# sch_camera.net
KiCad netlist of a schematic drawn in Altium Designer
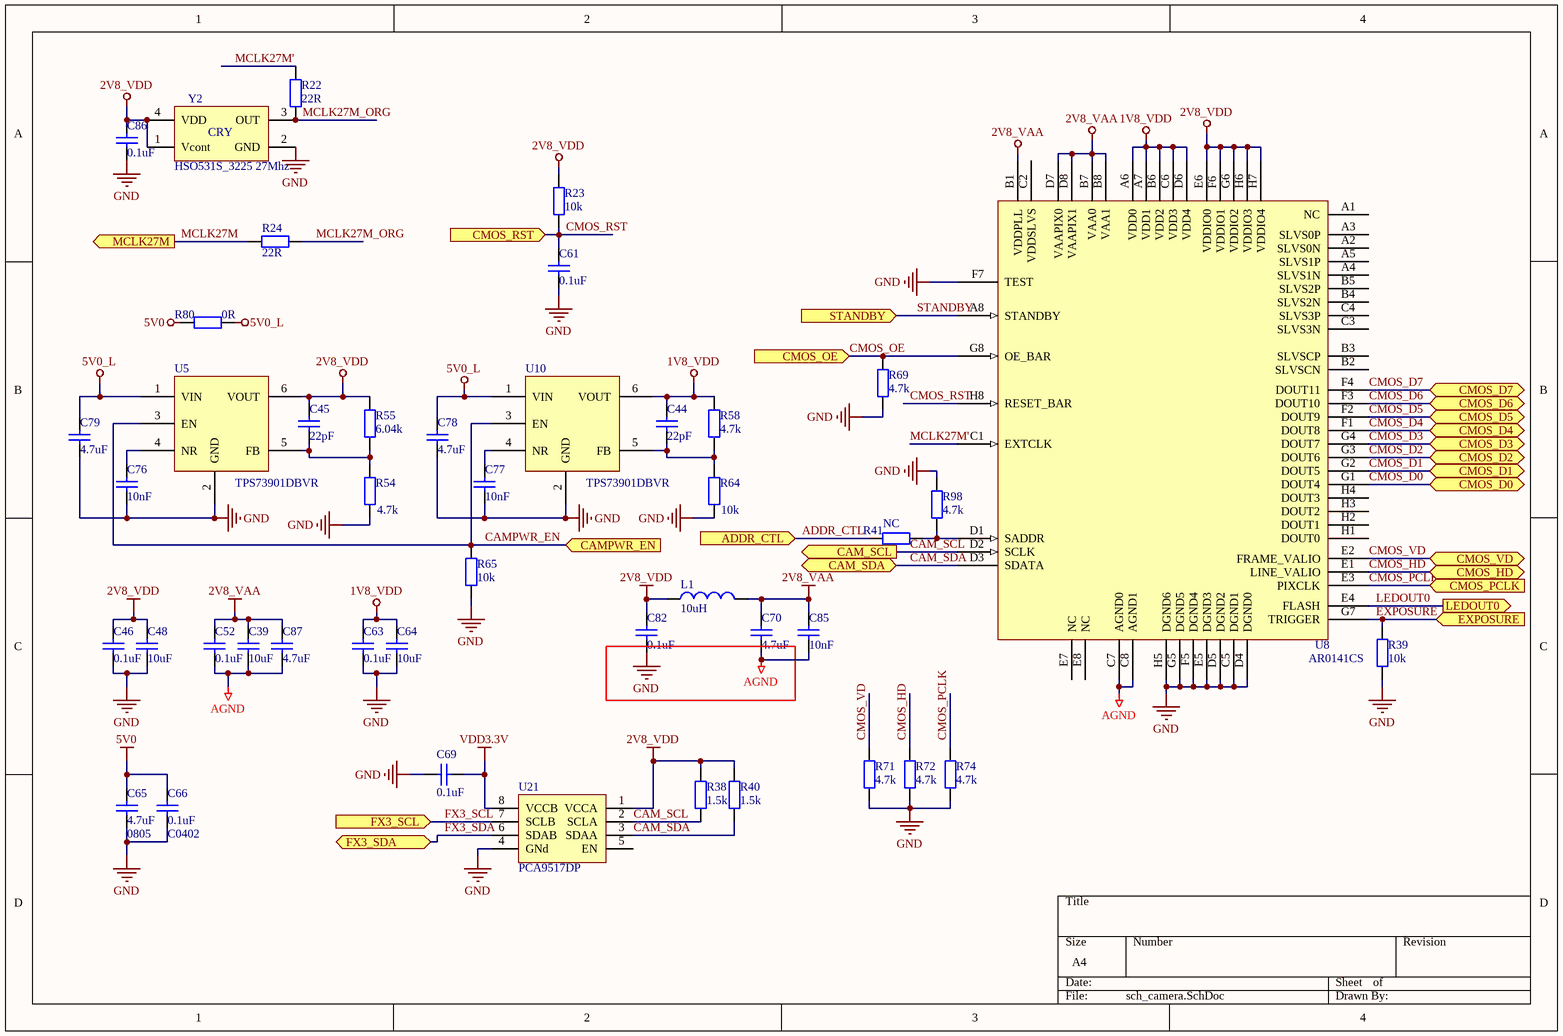
[diagram p0: sch_camera.SchDoc]

(export (version "E")
  (design (tool "Eeschema 10.0.6"))
  (components
    (comp (ref "C39")
      (value "10uF")
      (footprint "0805C")
      (description "Capacitor")
      (fields (field (name "PUBLISHER") "Altium Limited"))
      (libsource (lib "Miscellaneous Devices") (part "Cap"))
    )
    (comp (ref "C44")
      (value "22pF")
      (footprint "0402C")
      (description "Capacitor")
      (fields (field (name "PUBLISHER") "Altium Limited"))
      (libsource (lib "Miscellaneous Devices") (part "Cap"))
    )
    (comp (ref "C45")
      (value "22pF")
      (footprint "0805C")
      (description "Capacitor")
      (fields (field (name "PUBLISHER") "Altium Limited"))
      (libsource (lib "Miscellaneous Devices") (part "Cap"))
    )
    (comp (ref "C46")
      (value "0.1uF")
      (footprint "0402C")
      (description "Capacitor")
      (fields (field (name "PUBLISHER") "Altium Limited"))
      (libsource (lib "Miscellaneous Devices") (part "Cap"))
    )
    (comp (ref "C48")
      (value "10uF")
      (footprint "0805C")
      (description "Capacitor")
      (fields (field (name "PUBLISHER") "Altium Limited"))
      (libsource (lib "Miscellaneous Devices") (part "Cap"))
    )
    (comp (ref "C52")
      (value "0.1uF")
      (footprint "0402C")
      (description "Capacitor")
      (fields (field (name "PUBLISHER") "Altium Limited"))
      (libsource (lib "Miscellaneous Devices") (part "Cap"))
    )
    (comp (ref "C61")
      (value "0.1uF")
      (footprint "0402C_L")
      (description "Capacitor")
      (fields (field (name "PUBLISHER") "Altium Limited"))
      (libsource (lib "Miscellaneous Devices") (part "Cap"))
    )
    (comp (ref "C63")
      (value "0.1uF")
      (footprint "0402C")
      (description "Capacitor")
      (fields (field (name "PUBLISHER") "Altium Limited"))
      (libsource (lib "Miscellaneous Devices") (part "Cap"))
    )
    (comp (ref "C64")
      (value "10uF")
      (footprint "0805C")
      (description "Capacitor")
      (fields (field (name "PUBLISHER") "Altium Limited"))
      (libsource (lib "Miscellaneous Devices") (part "Cap"))
    )
    (comp (ref "C65")
      (value "4.7uF")
      (footprint "0805C")
      (description "Capacitor")
      (fields (field (name "ALTIUM_VALUE") "0805") (field (name "PUBLISHER") "Altium Limited"))
      (libsource (lib "Miscellaneous Devices") (part "Cap"))
    )
    (comp (ref "C66")
      (value "0.1uF")
      (footprint "0402C")
      (description "Capacitor")
      (fields (field (name "ALTIUM_VALUE") "C0402") (field (name "PUBLISHER") "Altium Limited"))
      (libsource (lib "Miscellaneous Devices") (part "Cap"))
    )
    (comp (ref "C69")
      (value "0.1uF")
      (footprint "0402C")
      (description "Capacitor")
      (fields (field (name "PUBLISHER") "Altium Limited"))
      (libsource (lib "Miscellaneous Devices") (part "Cap"))
    )
    (comp (ref "C70")
      (value "4.7uF")
      (footprint "0402C")
      (description "Capacitor")
      (fields (field (name "PUBLISHER") "Altium Limited"))
      (libsource (lib "Miscellaneous Devices") (part "Cap"))
    )
    (comp (ref "C76")
      (value "10nF")
      (footprint "0402C_L")
      (description "Capacitor")
      (fields (field (name "PUBLISHER") "Altium Limited"))
      (libsource (lib "Miscellaneous Devices") (part "Cap"))
    )
    (comp (ref "C77")
      (value "10nF")
      (footprint "0402C_L")
      (description "Capacitor")
      (fields (field (name "PUBLISHER") "Altium Limited"))
      (libsource (lib "Miscellaneous Devices") (part "Cap"))
    )
    (comp (ref "C78")
      (value "4.7uF")
      (footprint "0402C_L")
      (description "Capacitor")
      (fields (field (name "Comment") "1uF") (field (name "PUBLISHER") "Altium Limited"))
      (libsource (lib "Miscellaneous Devices") (part "Cap"))
    )
    (comp (ref "C79")
      (value "4.7uF")
      (footprint "0402C_L")
      (description "Capacitor")
      (fields (field (name "Comment") "1uF") (field (name "PUBLISHER") "Altium Limited"))
      (libsource (lib "Miscellaneous Devices") (part "Cap"))
    )
    (comp (ref "C82")
      (value "0.1uF")
      (footprint "0402C_L")
      (description "Capacitor")
      (fields (field (name "PUBLISHER") "Altium Limited"))
      (libsource (lib "Miscellaneous Devices") (part "Cap"))
    )
    (comp (ref "C85")
      (value "10nF")
      (footprint "0402C_L")
      (description "Capacitor")
      (fields (field (name "PUBLISHER") "Altium Limited"))
      (libsource (lib "Miscellaneous Devices") (part "Cap"))
    )
    (comp (ref "C86")
      (value "0.1uF")
      (footprint "0402C_L")
      (description "Capacitor")
      (fields (field (name "PUBLISHER") "Altium Limited"))
      (libsource (lib "Miscellaneous Devices") (part "Cap"))
    )
    (comp (ref "C87")
      (value "4.7uF")
      (description "Capacitor")
      (fields (field (name "PUBLISHER") "Altium Limited"))
      (libsource (lib "Miscellaneous Devices") (part "Cap"))
    )
    (comp (ref "L1")
      (value "10uH")
      (footprint "0805R")
      (description "Inductor")
      (libsource (lib "SWUST_ROBOT") (part "Inductor"))
    )
    (comp (ref "R22")
      (value "22R")
      (footprint "0402R_L")
      (description "Resistor")
      (fields (field (name "Comment") "0R") (field (name "PUBLISHER") "Altium Limited"))
      (libsource (lib "") (part "Resistor_1"))
    )
    (comp (ref "R23")
      (value "10k")
      (footprint "0402R_L")
      (description "Resistor")
      (fields (field (name "Comment") "10K") (field (name "PUBLISHER") "Altium Limited"))
      (libsource (lib "") (part "Resistor_3"))
    )
    (comp (ref "R24")
      (value "22R")
      (footprint "0402R")
      (description "Resistor")
      (fields (field (name "PUBLISHER") "Altium Limited"))
      (libsource (lib "") (part "Resistor_2"))
    )
    (comp (ref "R38")
      (value "1.5k")
      (footprint "0402R_L")
      (description "Resistor")
      (fields (field (name "Comment") "1.5K") (field (name "PUBLISHER") "Altium Limited"))
      (libsource (lib "") (part "Resistor_3"))
    )
    (comp (ref "R39")
      (value "10k")
      (footprint "0402R_L")
      (description "Resistor")
      (fields (field (name "Comment") "10K") (field (name "PUBLISHER") "Altium Limited"))
      (libsource (lib "") (part "Resistor_1"))
    )
    (comp (ref "R40")
      (value "1.5k")
      (footprint "0402R_L")
      (description "Resistor")
      (fields (field (name "Comment") "1.5K") (field (name "PUBLISHER") "Altium Limited"))
      (libsource (lib "") (part "Resistor_3"))
    )
    (comp (ref "R41")
      (value "NC")
      (footprint "0402R_L")
      (description "Resistor")
      (fields (field (name "PUBLISHER") "Altium Limited"))
      (libsource (lib "") (part "Resistor_4"))
    )
    (comp (ref "R54")
      (value "4.7k")
      (footprint "0402R")
      (description "Resistor")
      (fields (field (name "Comment") "4.7K") (field (name "PUBLISHER") "Altium Limited"))
      (libsource (lib "") (part "Resistor_1"))
    )
    (comp (ref "R55")
      (value "6.04k")
      (footprint "0402R")
      (description "Resistor")
      (fields (field (name "Comment") "6.04K") (field (name "PUBLISHER") "Altium Limited"))
      (libsource (lib "") (part "Resistor_3"))
    )
    (comp (ref "R58")
      (value "4.7k")
      (footprint "0402R")
      (description "Resistor")
      (fields (field (name "Comment") "4.7K") (field (name "PUBLISHER") "Altium Limited"))
      (libsource (lib "") (part "Resistor_3"))
    )
    (comp (ref "R64")
      (value "10k")
      (footprint "0402R")
      (description "Resistor")
      (fields (field (name "Comment") "10K") (field (name "PUBLISHER") "Altium Limited"))
      (libsource (lib "") (part "Resistor_1"))
    )
    (comp (ref "R65")
      (value "10k")
      (footprint "0402R_L")
      (description "Resistor")
      (fields (field (name "Comment") "10K") (field (name "PUBLISHER") "Altium Limited"))
      (libsource (lib "SZG") (part "Resistor"))
    )
    (comp (ref "R69")
      (value "4.7k")
      (footprint "0402R_L")
      (description "Resistor")
      (fields (field (name "Comment") "4.7K") (field (name "PUBLISHER") "Altium Limited"))
      (libsource (lib "") (part "Resistor_3"))
    )
    (comp (ref "R71")
      (value "4.7k")
      (footprint "0402R_L")
      (description "Resistor")
      (fields (field (name "Comment") "4.7K") (field (name "PUBLISHER") "Altium Limited"))
      (libsource (lib "") (part "Resistor_1"))
    )
    (comp (ref "R72")
      (value "4.7k")
      (footprint "0402R_L")
      (description "Resistor")
      (fields (field (name "Comment") "4.7K") (field (name "PUBLISHER") "Altium Limited"))
      (libsource (lib "") (part "Resistor_1"))
    )
    (comp (ref "R74")
      (value "4.7k")
      (footprint "0402R_L")
      (description "Resistor")
      (fields (field (name "Comment") "4.7K") (field (name "PUBLISHER") "Altium Limited"))
      (libsource (lib "") (part "Resistor_1"))
    )
    (comp (ref "R80")
      (value "0R")
      (footprint "0402R")
      (description "Resistor")
      (fields (field (name "PUBLISHER") "Altium Limited"))
      (libsource (lib "") (part "Resistor_2"))
    )
    (comp (ref "R98")
      (value "4.7k")
      (footprint "0402R_L")
      (description "Resistor")
      (fields (field (name "Comment") "4.7K") (field (name "PUBLISHER") "Altium Limited"))
      (libsource (lib "") (part "Resistor_1"))
    )
    (comp (ref "U5") (value "TPS73901DBVR") (libsource (lib "SZG") (part "TPS73901DBVR")))
    (comp (ref "U8") (value "AR0141CS") (libsource (lib "TXW") (part "AR0141CS")))
    (comp (ref "U10") (value "TPS73901DBVR") (libsource (lib "SZG") (part "TPS73901DBVR")))
    (comp (ref "U21") (value "PCA9517DP") (libsource (lib "SZG") (part "PCA9517DP")))
    (comp (ref "Y2")
      (value "HSO531S_3225 27Mhz")
      (footprint "XTAL_3225")
      (description "有源晶振")
      (libsource (lib "超集元件库") (part "CRY"))
    )
  )
  (nets
    (net (code "1") (name "/ADDR_CTL") (class "Default")
      (node (ref "R41") (pin "2") (pinfunction "2_2") (pintype "passive"))
    )
    (net (code "2") (name "/CAMPWR_EN") (class "Default")
      (node (ref "R65") (pin "1") (pinfunction "1_1") (pintype "passive"))
      (node (ref "U10") (pin "3") (pinfunction "EN_3") (pintype "passive"))
      (node (ref "U5") (pin "3") (pinfunction "EN_3") (pintype "passive"))
    )
    (net (code "3") (name "/CAM_SCL") (class "Default")
      (node (ref "R38") (pin "1") (pinfunction "1_1") (pintype "passive"))
      (node (ref "U21") (pin "2") (pinfunction "SCLA_2") (pintype "passive"))
      (node (ref "U8") (pin "D2") (pinfunction "SCLK_D2") (pintype "input"))
    )
    (net (code "4") (name "/CAM_SDA") (class "Default")
      (node (ref "R40") (pin "1") (pinfunction "1_1") (pintype "passive"))
      (node (ref "U21") (pin "3") (pinfunction "SDAA_3") (pintype "passive"))
      (node (ref "U8") (pin "D3") (pinfunction "SDATA_D3") (pintype "passive"))
    )
    (net (code "5") (name "/CMOS_D0") (class "Default")
      (node (ref "U8") (pin "G1") (pinfunction "DOUT4_G1") (pintype "passive"))
    )
    (net (code "6") (name "/CMOS_D1") (class "Default")
      (node (ref "U8") (pin "G2") (pinfunction "DOUT5_G2") (pintype "passive"))
    )
    (net (code "7") (name "/CMOS_D2") (class "Default")
      (node (ref "U8") (pin "G3") (pinfunction "DOUT6_G3") (pintype "passive"))
    )
    (net (code "8") (name "/CMOS_D3") (class "Default")
      (node (ref "U8") (pin "G4") (pinfunction "DOUT7_G4") (pintype "passive"))
    )
    (net (code "9") (name "/CMOS_D4") (class "Default")
      (node (ref "U8") (pin "F1") (pinfunction "DOUT8_F1") (pintype "passive"))
    )
    (net (code "10") (name "/CMOS_D5") (class "Default")
      (node (ref "U8") (pin "F2") (pinfunction "DOUT9_F2") (pintype "passive"))
    )
    (net (code "11") (name "/CMOS_D6") (class "Default")
      (node (ref "U8") (pin "F3") (pinfunction "DOUT10_F3") (pintype "passive"))
    )
    (net (code "12") (name "/CMOS_D7") (class "Default")
      (node (ref "U8") (pin "F4") (pinfunction "DOUT11_F4") (pintype "passive"))
    )
    (net (code "13") (name "/CMOS_HD") (class "Default")
      (node (ref "R72") (pin "1") (pinfunction "1_1") (pintype "passive"))
      (node (ref "U8") (pin "E1") (pinfunction "LINE_VALIO_E1") (pintype "passive"))
    )
    (net (code "14") (name "/CMOS_OE") (class "Default")
      (node (ref "R69") (pin "2") (pinfunction "2_2") (pintype "passive"))
      (node (ref "U8") (pin "G8") (pinfunction "OE_BAR_G8") (pintype "input"))
    )
    (net (code "15") (name "/CMOS_PCLK") (class "Default")
      (node (ref "R74") (pin "1") (pinfunction "1_1") (pintype "passive"))
      (node (ref "U8") (pin "E3") (pinfunction "PIXCLK_E3") (pintype "passive"))
    )
    (net (code "16") (name "/CMOS_RST") (class "Default")
      (node (ref "C61") (pin "2") (pinfunction "2_2") (pintype "passive"))
      (node (ref "R23") (pin "1") (pinfunction "1_1") (pintype "passive"))
      (node (ref "U8") (pin "H8") (pinfunction "RESET_BAR_H8") (pintype "input"))
    )
    (net (code "17") (name "/CMOS_VD") (class "Default")
      (node (ref "R71") (pin "1") (pinfunction "1_1") (pintype "passive"))
      (node (ref "U8") (pin "E2") (pinfunction "FRAME_VALIO_E2") (pintype "passive"))
    )
    (net (code "18") (name "/EXPOSURE") (class "Default")
      (node (ref "R39") (pin "1") (pinfunction "1_1") (pintype "passive"))
      (node (ref "U8") (pin "G7") (pinfunction "TRIGGER_G7") (pintype "passive"))
    )
    (net (code "19") (name "/FX3_SCL") (class "Default")
      (node (ref "U21") (pin "7") (pinfunction "SCLB_7") (pintype "passive"))
    )
    (net (code "20") (name "/FX3_SDA") (class "Default")
      (node (ref "U21") (pin "6") (pinfunction "SDAB_6") (pintype "passive"))
    )
    (net (code "21") (name "/LEDOUT0") (class "Default")
      (node (ref "U8") (pin "E4") (pinfunction "FLASH_E4") (pintype "passive"))
    )
    (net (code "22") (name "/MCLK27M") (class "Default")
      (node (ref "R24") (pin "1") (pinfunction "1_1") (pintype "passive"))
    )
    (net (code "23") (name "/MCLK27M'") (class "Default")
      (node (ref "R22") (pin "1") (pinfunction "1_1") (pintype "passive"))
      (node (ref "U8") (pin "C1") (pinfunction "EXTCLK_C1") (pintype "input"))
    )
    (net (code "24") (name "/MCLK27M_ORG") (class "Default")
      (node (ref "R22") (pin "2") (pinfunction "2_2") (pintype "passive"))
      (node (ref "R24") (pin "2") (pinfunction "2_2") (pintype "passive"))
      (node (ref "Y2") (pin "3") (pinfunction "OUT_3") (pintype "passive"))
    )
    (net (code "25") (name "/STANDBY") (class "Default")
      (node (ref "U8") (pin "A8") (pinfunction "STANDBY_A8") (pintype "input"))
    )
    (net (code "26") (name "1V8_VDD") (class "Default")
      (node (ref "C44") (pin "2") (pinfunction "2_2") (pintype "passive"))
      (node (ref "C63") (pin "2") (pinfunction "2_2") (pintype "passive"))
      (node (ref "C64") (pin "2") (pinfunction "2_2") (pintype "passive"))
      (node (ref "R58") (pin "2") (pinfunction "2_2") (pintype "passive"))
      (node (ref "U10") (pin "6") (pinfunction "VOUT_6") (pintype "passive"))
      (node (ref "U8") (pin "A6") (pinfunction "VDD0_A6") (pintype "power_in"))
      (node (ref "U8") (pin "A7") (pinfunction "VDD1_A7") (pintype "power_in"))
      (node (ref "U8") (pin "B6") (pinfunction "VDD2_B6") (pintype "power_in"))
      (node (ref "U8") (pin "C6") (pinfunction "VDD3_C6") (pintype "power_in"))
      (node (ref "U8") (pin "D6") (pinfunction "VDD4_D6") (pintype "power_in"))
    )
    (net (code "27") (name "2V8_VAA") (class "Default")
      (node (ref "C39") (pin "2") (pinfunction "2_2") (pintype "passive"))
      (node (ref "C52") (pin "2") (pinfunction "2_2") (pintype "passive"))
      (node (ref "C70") (pin "2") (pinfunction "2_2") (pintype "passive"))
      (node (ref "C85") (pin "2") (pinfunction "2_2") (pintype "passive"))
      (node (ref "C87") (pin "2") (pinfunction "2_2") (pintype "passive"))
      (node (ref "L1") (pin "2") (pinfunction "2_2") (pintype "passive"))
      (node (ref "U8") (pin "B1") (pinfunction "VDDPLL_B1") (pintype "power_in"))
      (node (ref "U8") (pin "B7") (pinfunction "VAA0_B7") (pintype "power_in"))
      (node (ref "U8") (pin "B8") (pinfunction "VAA1_B8") (pintype "power_in"))
      (node (ref "U8") (pin "D7") (pinfunction "VAAPIX0_D7") (pintype "power_in"))
      (node (ref "U8") (pin "D8") (pinfunction "VAAPIX1_D8") (pintype "power_in"))
    )
    (net (code "28") (name "2V8_VDD") (class "Default")
      (node (ref "C45") (pin "2") (pinfunction "2_2") (pintype "passive"))
      (node (ref "C46") (pin "2") (pinfunction "2_2") (pintype "passive"))
      (node (ref "C48") (pin "2") (pinfunction "2_2") (pintype "passive"))
      (node (ref "C82") (pin "2") (pinfunction "2_2") (pintype "passive"))
      (node (ref "C86") (pin "2") (pinfunction "2_2") (pintype "passive"))
      (node (ref "L1") (pin "1") (pinfunction "1_1") (pintype "passive"))
      (node (ref "R23") (pin "2") (pinfunction "2_2") (pintype "passive"))
      (node (ref "R38") (pin "2") (pinfunction "2_2") (pintype "passive"))
      (node (ref "R40") (pin "2") (pinfunction "2_2") (pintype "passive"))
      (node (ref "R55") (pin "2") (pinfunction "2_2") (pintype "passive"))
      (node (ref "U21") (pin "1") (pinfunction "VCCA_1") (pintype "power_in"))
      (node (ref "U5") (pin "6") (pinfunction "VOUT_6") (pintype "passive"))
      (node (ref "U8") (pin "E6") (pinfunction "VDDIO0_E6") (pintype "power_in"))
      (node (ref "U8") (pin "F6") (pinfunction "VDDIO1_F6") (pintype "power_in"))
      (node (ref "U8") (pin "G6") (pinfunction "VDDIO2_G6") (pintype "power_in"))
      (node (ref "U8") (pin "H6") (pinfunction "VDDIO3_H6") (pintype "power_in"))
      (node (ref "U8") (pin "H7") (pinfunction "VDDIO4_H7") (pintype "power_in"))
      (node (ref "Y2") (pin "1") (pinfunction "Vcont_1") (pintype "passive"))
      (node (ref "Y2") (pin "4") (pinfunction "VDD_4") (pintype "passive"))
    )
    (net (code "29") (name "5V0") (class "Default")
      (node (ref "C65") (pin "2") (pinfunction "2_2") (pintype "passive"))
      (node (ref "C66") (pin "2") (pinfunction "2_2") (pintype "passive"))
      (node (ref "R80") (pin "1") (pinfunction "1_1") (pintype "passive"))
    )
    (net (code "30") (name "5V0_L") (class "Default")
      (node (ref "C78") (pin "2") (pinfunction "2_2") (pintype "passive"))
      (node (ref "C79") (pin "2") (pinfunction "2_2") (pintype "passive"))
      (node (ref "R80") (pin "2") (pinfunction "2_2") (pintype "passive"))
      (node (ref "U10") (pin "1") (pinfunction "VIN_1") (pintype "passive"))
      (node (ref "U5") (pin "1") (pinfunction "VIN_1") (pintype "passive"))
    )
    (net (code "31") (name "AGND") (class "Default")
      (node (ref "C39") (pin "1") (pinfunction "1_1") (pintype "passive"))
      (node (ref "C52") (pin "1") (pinfunction "1_1") (pintype "passive"))
      (node (ref "C70") (pin "1") (pinfunction "1_1") (pintype "passive"))
      (node (ref "C85") (pin "1") (pinfunction "1_1") (pintype "passive"))
      (node (ref "C87") (pin "1") (pinfunction "1_1") (pintype "passive"))
      (node (ref "U8") (pin "C7") (pinfunction "AGND0_C7") (pintype "power_in"))
      (node (ref "U8") (pin "C8") (pinfunction "AGND1_C8") (pintype "power_in"))
    )
    (net (code "32") (name "GND") (class "Default")
      (node (ref "C46") (pin "1") (pinfunction "1_1") (pintype "passive"))
      (node (ref "C48") (pin "1") (pinfunction "1_1") (pintype "passive"))
      (node (ref "C61") (pin "1") (pinfunction "1_1") (pintype "passive"))
      (node (ref "C63") (pin "1") (pinfunction "1_1") (pintype "passive"))
      (node (ref "C64") (pin "1") (pinfunction "1_1") (pintype "passive"))
      (node (ref "C65") (pin "1") (pinfunction "1_1") (pintype "passive"))
      (node (ref "C66") (pin "1") (pinfunction "1_1") (pintype "passive"))
      (node (ref "C69") (pin "2") (pinfunction "2_2") (pintype "passive"))
      (node (ref "C76") (pin "1") (pinfunction "1_1") (pintype "passive"))
      (node (ref "C77") (pin "1") (pinfunction "1_1") (pintype "passive"))
      (node (ref "C78") (pin "1") (pinfunction "1_1") (pintype "passive"))
      (node (ref "C79") (pin "1") (pinfunction "1_1") (pintype "passive"))
      (node (ref "C82") (pin "1") (pinfunction "1_1") (pintype "passive"))
      (node (ref "C86") (pin "1") (pinfunction "1_1") (pintype "passive"))
      (node (ref "R39") (pin "2") (pinfunction "2_2") (pintype "passive"))
      (node (ref "R54") (pin "2") (pinfunction "2_2") (pintype "passive"))
      (node (ref "R64") (pin "2") (pinfunction "2_2") (pintype "passive"))
      (node (ref "R65") (pin "2") (pinfunction "2_2") (pintype "passive"))
      (node (ref "R69") (pin "1") (pinfunction "1_1") (pintype "passive"))
      (node (ref "R71") (pin "2") (pinfunction "2_2") (pintype "passive"))
      (node (ref "R72") (pin "2") (pinfunction "2_2") (pintype "passive"))
      (node (ref "R74") (pin "2") (pinfunction "2_2") (pintype "passive"))
      (node (ref "R98") (pin "1") (pinfunction "1_1") (pintype "passive"))
      (node (ref "U10") (pin "2") (pinfunction "GND_2") (pintype "passive"))
      (node (ref "U21") (pin "4") (pinfunction "GNd_4") (pintype "power_in"))
      (node (ref "U5") (pin "2") (pinfunction "GND_2") (pintype "passive"))
      (node (ref "U8") (pin "C5") (pinfunction "DGND1_C5") (pintype "power_in"))
      (node (ref "U8") (pin "D4") (pinfunction "DGND0_D4") (pintype "power_in"))
      (node (ref "U8") (pin "D5") (pinfunction "DGND2_D5") (pintype "power_in"))
      (node (ref "U8") (pin "E5") (pinfunction "DGND3_E5") (pintype "power_in"))
      (node (ref "U8") (pin "F5") (pinfunction "DGND4_F5") (pintype "power_in"))
      (node (ref "U8") (pin "F7") (pinfunction "TEST_F7") (pintype "passive"))
      (node (ref "U8") (pin "G5") (pinfunction "DGND5_G5") (pintype "power_in"))
      (node (ref "U8") (pin "H5") (pinfunction "DGND6_H5") (pintype "power_in"))
      (node (ref "Y2") (pin "2") (pinfunction "GND_2") (pintype "passive"))
    )
    (net (code "33") (name "Net-(U5-FB)") (class "Default")
      (node (ref "C45") (pin "1") (pinfunction "1_1") (pintype "passive"))
      (node (ref "R54") (pin "1") (pinfunction "1_1") (pintype "passive"))
      (node (ref "R55") (pin "1") (pinfunction "1_1") (pintype "passive"))
      (node (ref "U5") (pin "5") (pinfunction "FB_5") (pintype "passive"))
    )
    (net (code "34") (name "Net-(U5-NR)") (class "Default")
      (node (ref "C76") (pin "2") (pinfunction "2_2") (pintype "passive"))
      (node (ref "U5") (pin "4") (pinfunction "NR_4") (pintype "passive"))
    )
    (net (code "35") (name "Net-(U8-SADDR)") (class "Default")
      (node (ref "R41") (pin "1") (pinfunction "1_1") (pintype "passive"))
      (node (ref "R98") (pin "2") (pinfunction "2_2") (pintype "passive"))
      (node (ref "U8") (pin "D1") (pinfunction "SADDR_D1") (pintype "input"))
    )
    (net (code "36") (name "Net-(U10-FB)") (class "Default")
      (node (ref "C44") (pin "1") (pinfunction "1_1") (pintype "passive"))
      (node (ref "R58") (pin "1") (pinfunction "1_1") (pintype "passive"))
      (node (ref "R64") (pin "1") (pinfunction "1_1") (pintype "passive"))
      (node (ref "U10") (pin "5") (pinfunction "FB_5") (pintype "passive"))
    )
    (net (code "37") (name "Net-(U10-NR)") (class "Default")
      (node (ref "C77") (pin "2") (pinfunction "2_2") (pintype "passive"))
      (node (ref "U10") (pin "4") (pinfunction "NR_4") (pintype "passive"))
    )
    (net (code "38") (name "VDD3.3V") (class "Default")
      (node (ref "C69") (pin "1") (pinfunction "1_1") (pintype "passive"))
      (node (ref "U21") (pin "8") (pinfunction "VCCB_8") (pintype "passive"))
    )
    (net (code "39") (name "unconnected-(U8-DOUT0-PadH1)") (class "Default")
      (node (ref "U8") (pin "H1") (pinfunction "DOUT0_H1") (pintype "passive"))
    )
    (net (code "40") (name "unconnected-(U8-DOUT1-PadH2)") (class "Default")
      (node (ref "U8") (pin "H2") (pinfunction "DOUT1_H2") (pintype "passive"))
    )
    (net (code "41") (name "unconnected-(U8-DOUT2-PadH3)") (class "Default")
      (node (ref "U8") (pin "H3") (pinfunction "DOUT2_H3") (pintype "passive"))
    )
    (net (code "42") (name "unconnected-(U8-DOUT3-PadH4)") (class "Default")
      (node (ref "U8") (pin "H4") (pinfunction "DOUT3_H4") (pintype "passive"))
    )
    (net (code "43") (name "unconnected-(U8-NC-PadA1)") (class "Default")
      (node (ref "U8") (pin "A1") (pinfunction "NC_A1") (pintype "passive"))
    )
    (net (code "44") (name "unconnected-(U8-NC-PadE7)") (class "Default")
      (node (ref "U8") (pin "E7") (pinfunction "NC_E7") (pintype "passive"))
    )
    (net (code "45") (name "unconnected-(U8-NC-PadE8)") (class "Default")
      (node (ref "U8") (pin "E8") (pinfunction "NC_E8") (pintype "passive"))
    )
    (net (code "46") (name "unconnected-(U8-SLVS0N-PadA2)") (class "Default")
      (node (ref "U8") (pin "A2") (pinfunction "SLVS0N_A2") (pintype "passive"))
    )
    (net (code "47") (name "unconnected-(U8-SLVS0P-PadA3)") (class "Default")
      (node (ref "U8") (pin "A3") (pinfunction "SLVS0P_A3") (pintype "passive"))
    )
    (net (code "48") (name "unconnected-(U8-SLVS1N-PadA4)") (class "Default")
      (node (ref "U8") (pin "A4") (pinfunction "SLVS1N_A4") (pintype "passive"))
    )
    (net (code "49") (name "unconnected-(U8-SLVS1P-PadA5)") (class "Default")
      (node (ref "U8") (pin "A5") (pinfunction "SLVS1P_A5") (pintype "passive"))
    )
    (net (code "50") (name "unconnected-(U8-SLVS2N-PadB4)") (class "Default")
      (node (ref "U8") (pin "B4") (pinfunction "SLVS2N_B4") (pintype "passive"))
    )
    (net (code "51") (name "unconnected-(U8-SLVS2P-PadB5)") (class "Default")
      (node (ref "U8") (pin "B5") (pinfunction "SLVS2P_B5") (pintype "passive"))
    )
    (net (code "52") (name "unconnected-(U8-SLVS3N-PadC3)") (class "Default")
      (node (ref "U8") (pin "C3") (pinfunction "SLVS3N_C3") (pintype "passive"))
    )
    (net (code "53") (name "unconnected-(U8-SLVS3P-PadC4)") (class "Default")
      (node (ref "U8") (pin "C4") (pinfunction "SLVS3P_C4") (pintype "passive"))
    )
    (net (code "54") (name "unconnected-(U8-SLVSCN-PadB2)") (class "Default")
      (node (ref "U8") (pin "B2") (pinfunction "SLVSCN_B2") (pintype "passive"))
    )
    (net (code "55") (name "unconnected-(U8-SLVSCP-PadB3)") (class "Default")
      (node (ref "U8") (pin "B3") (pinfunction "SLVSCP_B3") (pintype "passive"))
    )
    (net (code "56") (name "unconnected-(U8-VDDSLVS-PadC2)") (class "Default")
      (node (ref "U8") (pin "C2") (pinfunction "VDDSLVS_C2") (pintype "power_in"))
    )
    (net (code "57") (name "unconnected-(U21-EN-Pad5)") (class "Default")
      (node (ref "U21") (pin "5") (pinfunction "EN_5") (pintype "passive"))
    )
  )
)
